# BUCK5.net
KiCad netlist of a schematic drawn in EAGLE
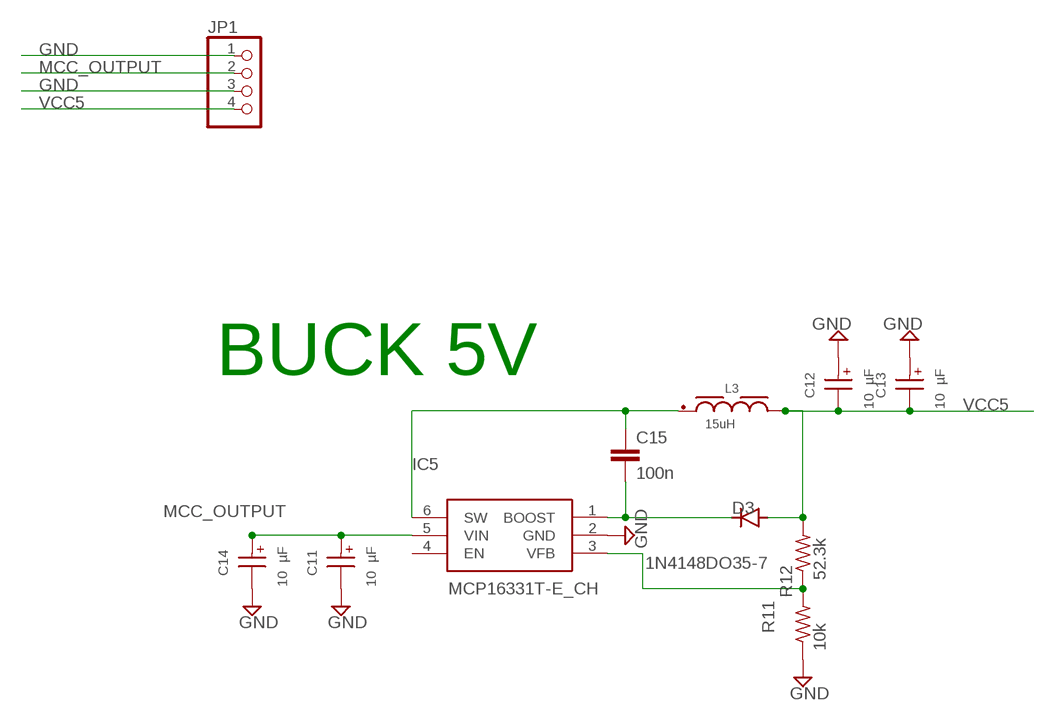
[diagram p0: schematic, sheet 1]

(export (version "E")
  (design (tool "Eeschema 10.0.6"))
  (components
    (comp (ref "C11")
      (value "10 µF")
      (footprint "eagle-import:WCAP-ASLI_6.3X7.7(DXL)")
      (libsource (lib "eagle-import") (part "WCAP-ASLI_6.3X7.7_865080845005"))
    )
    (comp (ref "C12")
      (value "10 µF")
      (footprint "eagle-import:WCAP-ASLI_6.3X7.7(DXL)")
      (libsource (lib "eagle-import") (part "WCAP-ASLI_6.3X7.7_865080845005"))
    )
    (comp (ref "C13")
      (value "10 µF")
      (footprint "eagle-import:WCAP-ASLI_6.3X7.7(DXL)")
      (libsource (lib "eagle-import") (part "WCAP-ASLI_6.3X7.7_865080845005"))
    )
    (comp (ref "C14")
      (value "10 µF")
      (footprint "eagle-import:WCAP-ASLI_6.3X7.7(DXL)")
      (libsource (lib "eagle-import") (part "WCAP-ASLI_6.3X7.7_865080845005"))
    )
    (comp (ref "C15")
      (value "100n")
      (footprint "eagle-import:C0805")
      (libsource (lib "eagle-import") (part "C-EUC0805"))
    )
    (comp (ref "D3")
      (value "1N4148DO35-7")
      (footprint "eagle-import:DO35-7")
      (libsource (lib "eagle-import") (part "1N4148DO35-7"))
    )
    (comp (ref "IC5")
      (value "MCP16331T-E_CH")
      (footprint "eagle-import:SOT95P280X145-6N")
      (fields
        (field (name "ARROW_PART_NUMBER") "MCP16331T-E/CH")
        (field (name "MOUSER_PART_NUMBER") "579-MCP16331T-E/CH")
      )
      (libsource (lib "eagle-import") (part "MCP16331T-E_CH"))
    )
    (comp (ref "JP1")
      (value "PINHD-1X4")
      (footprint "eagle-import:1X04")
      (libsource (lib "eagle-import") (part "PINHD-1X4"))
    )
    (comp (ref "L3")
      (value "15uH")
      (footprint "eagle-import:WE-PD_7345R")
      (libsource (lib "eagle-import") (part "WE-PD_7345R_7447779115"))
    )
    (comp (ref "R11")
      (value "10k")
      (footprint "eagle-import:R0603")
      (libsource (lib "eagle-import") (part "R-US_R0603"))
    )
    (comp (ref "R12")
      (value "52.3k")
      (footprint "eagle-import:R0603")
      (libsource (lib "eagle-import") (part "R-US_R0603"))
    )
  )
  (nets
    (net (code "1") (name "/MCC_OUTPUT") (class "Default")
      (node (ref "C11") (pin "1") (pinfunction "+_1") (pintype "passive"))
      (node (ref "C14") (pin "1") (pinfunction "+_1") (pintype "passive"))
      (node (ref "IC5") (pin "5") (pinfunction "VIN_5") (pintype "bidirectional"))
      (node (ref "JP1") (pin "2") (pinfunction "2_2") (pintype "passive"))
    )
    (net (code "2") (name "/VCC5") (class "Default")
      (node (ref "C12") (pin "2") (pinfunction "-_2") (pintype "passive"))
      (node (ref "C13") (pin "2") (pinfunction "-_2") (pintype "passive"))
      (node (ref "D3") (pin "A") (pinfunction "A_A") (pintype "passive"))
      (node (ref "JP1") (pin "4") (pinfunction "4_4") (pintype "passive"))
      (node (ref "L3") (pin "2") (pinfunction "2_2") (pintype "passive"))
      (node (ref "R12") (pin "2") (pinfunction "2_2") (pintype "passive"))
    )
    (net (code "3") (name "GND") (class "Default")
      (node (ref "C11") (pin "2") (pinfunction "-_2") (pintype "passive"))
      (node (ref "C12") (pin "1") (pinfunction "+_1") (pintype "passive"))
      (node (ref "C13") (pin "1") (pinfunction "+_1") (pintype "passive"))
      (node (ref "C14") (pin "2") (pinfunction "-_2") (pintype "passive"))
      (node (ref "IC5") (pin "2") (pinfunction "GND_2") (pintype "bidirectional"))
      (node (ref "JP1") (pin "1") (pinfunction "1_1") (pintype "passive"))
      (node (ref "JP1") (pin "3") (pinfunction "3_3") (pintype "passive"))
      (node (ref "R11") (pin "1") (pinfunction "1_1") (pintype "passive"))
    )
    (net (code "4") (name "Net-(IC5-BOOST)") (class "Default")
      (node (ref "C15") (pin "2") (pinfunction "2_2") (pintype "passive"))
      (node (ref "D3") (pin "C") (pinfunction "C_C") (pintype "passive"))
      (node (ref "IC5") (pin "1") (pinfunction "BOOST_1") (pintype "bidirectional"))
    )
    (net (code "5") (name "Net-(IC5-SW)") (class "Default")
      (node (ref "C15") (pin "1") (pinfunction "1_1") (pintype "passive"))
      (node (ref "IC5") (pin "6") (pinfunction "SW_6") (pintype "bidirectional"))
      (node (ref "L3") (pin "1") (pinfunction "1_1") (pintype "passive"))
    )
    (net (code "6") (name "Net-(IC5-VFB)") (class "Default")
      (node (ref "IC5") (pin "3") (pinfunction "VFB_3") (pintype "bidirectional"))
      (node (ref "R11") (pin "2") (pinfunction "2_2") (pintype "passive"))
      (node (ref "R12") (pin "1") (pinfunction "1_1") (pintype "passive"))
    )
    (net (code "7") (name "unconnected-(IC5-EN-Pad4)") (class "Default")
      (node (ref "IC5") (pin "4") (pinfunction "EN_4") (pintype "bidirectional"))
    )
  )
)
